# main.net
KiCad netlist of a schematic drawn in Altium Designer
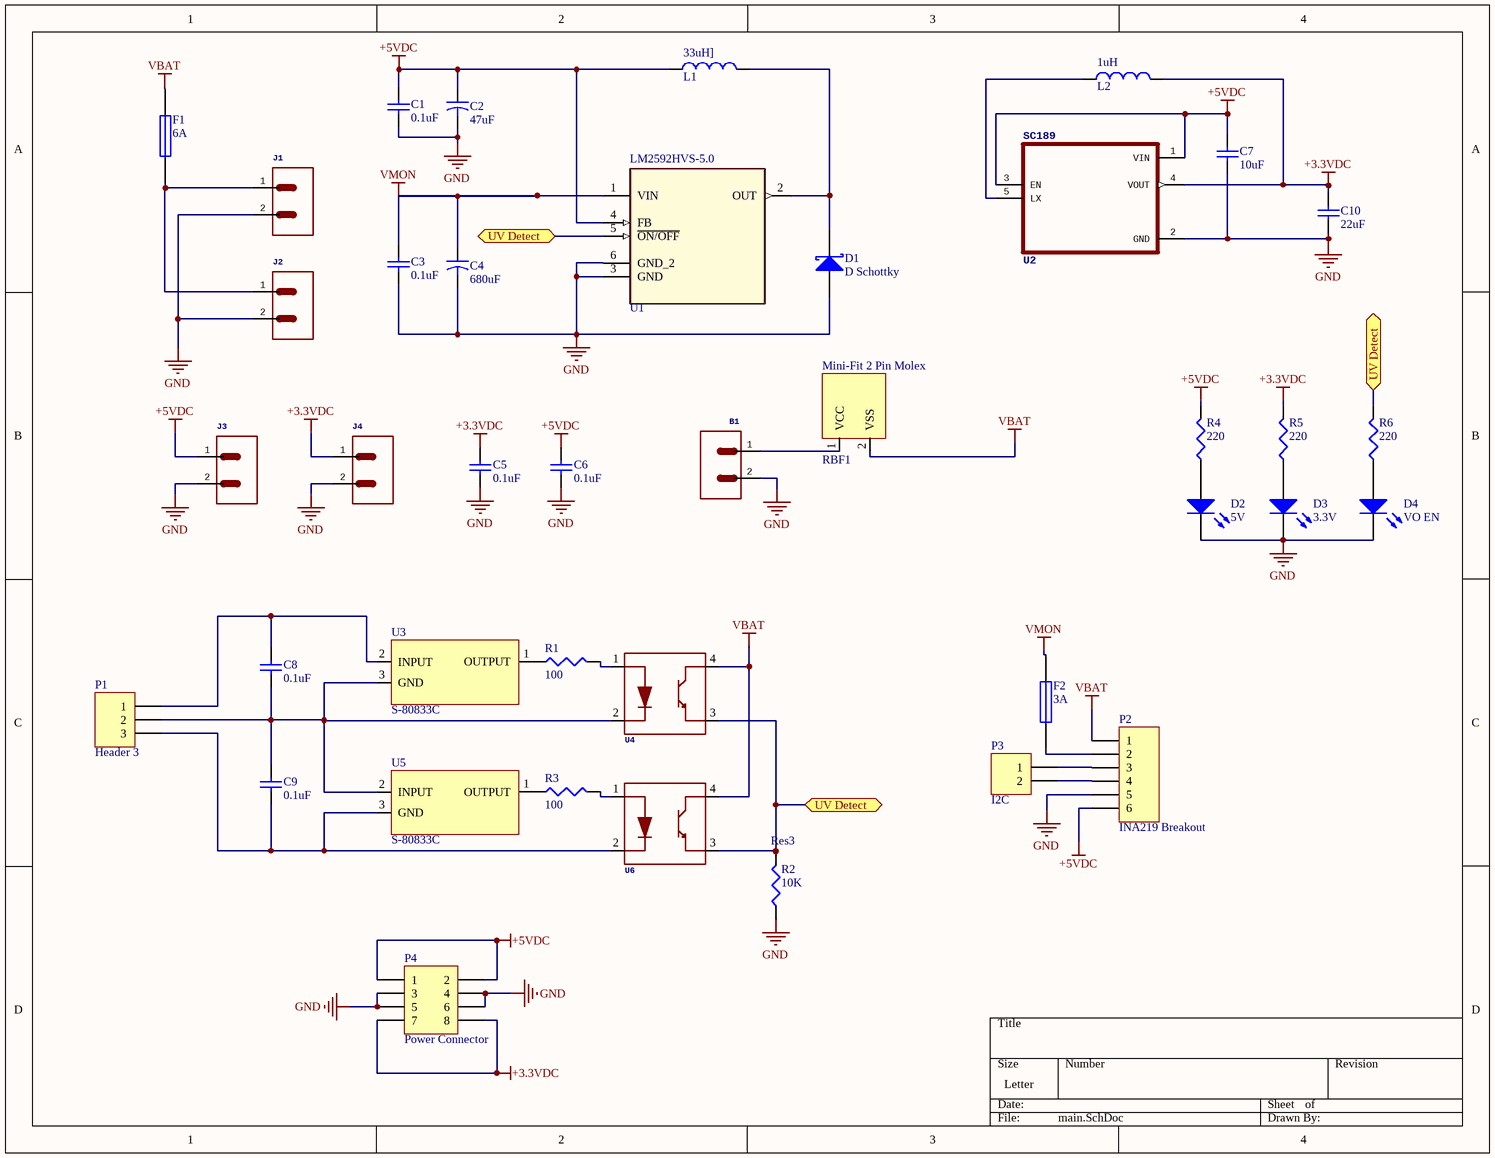
[diagram p0: main.SchDoc]

(export (version "E")
  (design (tool "Eeschema 10.0.6"))
  (components
    (comp (ref "B1")
      (value "15A 2P TERM BLOCK, BLACKtested: NO")
      (footprint "Mini-Fit 2 Pin Molex")
      (libsource (lib "Common-Parts-Library") (part "1760510000"))
    )
    (comp (ref "C1")
      (value "0.1uF")
      (footprint "C1206")
      (description "Capacitor (Semiconductor SIM Model)")
      (fields (field (name "Comment") "Cap Semi") (field (name "PUBLISHER") "Altium Limited"))
      (libsource (lib "Miscellaneous Devices") (part "Cap Semi"))
    )
    (comp (ref "C2")
      (value "47uF")
      (footprint "47 uF Cap")
      (description "Capacitor")
      (fields (field (name "Comment") "Cap2") (field (name "PUBLISHER") "Altium Limited"))
      (libsource (lib "Miscellaneous Devices") (part "Cap2"))
    )
    (comp (ref "C3")
      (value "0.1uF")
      (footprint "C1206")
      (description "Capacitor (Semiconductor SIM Model)")
      (fields (field (name "Comment") "Cap Semi") (field (name "PUBLISHER") "Altium Limited"))
      (libsource (lib "Miscellaneous Devices") (part "Cap Semi"))
    )
    (comp (ref "C4")
      (value "680uF")
      (footprint "680 uF Cap")
      (description "Capacitor")
      (fields (field (name "Comment") "Cap2") (field (name "PUBLISHER") "Altium Limited"))
      (libsource (lib "Miscellaneous Devices") (part "Cap2"))
    )
    (comp (ref "C5")
      (value "0.1uF")
      (footprint "C1206")
      (description "Capacitor (Semiconductor SIM Model)")
      (fields (field (name "Comment") "Cap Semi") (field (name "PUBLISHER") "Altium Limited"))
      (libsource (lib "Miscellaneous Devices") (part "Cap Semi"))
    )
    (comp (ref "C6")
      (value "0.1uF")
      (footprint "C1206")
      (description "Capacitor (Semiconductor SIM Model)")
      (fields (field (name "Comment") "Cap Semi") (field (name "PUBLISHER") "Altium Limited"))
      (libsource (lib "Miscellaneous Devices") (part "Cap Semi"))
    )
    (comp (ref "C7")
      (value "10uF")
      (footprint "C1206")
      (description "Capacitor (Semiconductor SIM Model)")
      (fields (field (name "Comment") "Cap Semi") (field (name "PUBLISHER") "Altium Limited"))
      (libsource (lib "Miscellaneous Devices") (part "Cap Semi"))
    )
    (comp (ref "C8")
      (value "0.1uF")
      (footprint "C1206")
      (description "Capacitor (Semiconductor SIM Model)")
      (fields (field (name "Comment") "Cap Semi") (field (name "PUBLISHER") "Altium Limited"))
      (libsource (lib "Miscellaneous Devices") (part "Cap Semi"))
    )
    (comp (ref "C9")
      (value "0.1uF")
      (footprint "C1206")
      (description "Capacitor (Semiconductor SIM Model)")
      (fields (field (name "Comment") "Cap Semi") (field (name "PUBLISHER") "Altium Limited"))
      (libsource (lib "Miscellaneous Devices") (part "Cap Semi"))
    )
    (comp (ref "C10")
      (value "22uF")
      (footprint "C1206")
      (description "Capacitor (Semiconductor SIM Model)")
      (fields (field (name "Comment") "Cap Semi") (field (name "PUBLISHER") "Altium Limited"))
      (libsource (lib "Miscellaneous Devices") (part "Cap Semi"))
    )
    (comp (ref "D1")
      (value "D Schottky")
      (footprint "SMB")
      (description "Schottky Diode")
      (fields (field (name "PUBLISHER") "Altium Limited"))
      (libsource (lib "Miscellaneous Devices") (part "D Schottky"))
    )
    (comp (ref "D2")
      (value "5V")
      (footprint "1608[0603]")
      (description "Typical RED GaAs LED")
      (fields (field (name "PUBLISHER") "Altium Limited"))
      (libsource (lib "Miscellaneous Devices") (part "LED1"))
    )
    (comp (ref "D3")
      (value "3.3V")
      (footprint "1608[0603]")
      (description "Typical RED GaAs LED")
      (fields (field (name "PUBLISHER") "Altium Limited"))
      (libsource (lib "Miscellaneous Devices") (part "LED1"))
    )
    (comp (ref "D4")
      (value "VO EN")
      (footprint "1608[0603]")
      (description "Typical RED GaAs LED")
      (fields (field (name "PUBLISHER") "Altium Limited"))
      (libsource (lib "Miscellaneous Devices") (part "LED1"))
    )
    (comp (ref "F1")
      (value "6A")
      (footprint "C1206")
      (description "Fuse")
      (fields (field (name "PUBLISHER") "Altium Limited"))
      (libsource (lib "Miscellaneous Devices") (part "Fuse 1"))
    )
    (comp (ref "F2")
      (value "3A")
      (footprint "J1-0603")
      (description "Fuse")
      (fields (field (name "PUBLISHER") "Altium Limited"))
      (libsource (lib "Miscellaneous Devices") (part "Fuse 1"))
    )
    (comp (ref "J1")
      (value "15A 2P TERM BLOCK, BLACKtested: NO")
      (footprint "1760490000")
      (libsource (lib "Common-Parts-Library") (part "1760510000"))
    )
    (comp (ref "J2")
      (value "15A 2P TERM BLOCK, BLACKtested: NO")
      (footprint "1760490000")
      (libsource (lib "Common-Parts-Library") (part "1760510000"))
    )
    (comp (ref "J3")
      (value "15A 2P TERM BLOCK, BLACKtested: NO")
      (footprint "1760490000")
      (libsource (lib "Common-Parts-Library") (part "1760510000"))
    )
    (comp (ref "J4")
      (value "15A 2P TERM BLOCK, BLACKtested: NO")
      (footprint "1760490000")
      (libsource (lib "Common-Parts-Library") (part "1760510000"))
    )
    (comp (ref "L1")
      (value "33uH]")
      (footprint "Inductor")
      (libsource (lib "CustomCompLib") (part "Inductor"))
    )
    (comp (ref "L2")
      (value "1uH")
      (footprint "INDC4532X34N")
      (libsource (lib "CustomCompLib") (part "Inductor"))
    )
    (comp (ref "P1")
      (value "Header 3")
      (footprint "HDR1X3")
      (description "Header, 3-Pin")
      (fields (field (name "PUBLISHER") "Altium Limited"))
      (libsource (lib "Miscellaneous Connectors") (part "Header 3"))
    )
    (comp (ref "P2")
      (value "INA219 Breakout")
      (footprint "HDR1X6")
      (description "Header, 6-Pin")
      (fields (field (name "PUBLISHER") "Altium Limited"))
      (libsource (lib "Miscellaneous Connectors") (part "Header 6"))
    )
    (comp (ref "P3")
      (value "I2C")
      (footprint "HDR1X2")
      (description "Header, 2-Pin")
      (fields (field (name "PUBLISHER") "Altium Limited"))
      (libsource (lib "Miscellaneous Connectors") (part "Header 2"))
    )
    (comp (ref "P4")
      (value "Power Connector")
      (footprint "HDR2X4")
      (description "Header, 4-Pin, Dual row")
      (fields (field (name "PUBLISHER") "Altium Limited"))
      (libsource (lib "Miscellaneous Connectors") (part "Header 4X2"))
    )
    (comp (ref "R1")
      (value "100")
      (footprint "J1-0603")
      (description "Resistor")
      (fields (field (name "Comment") "Res3") (field (name "PUBLISHER") "Altium Limited"))
      (libsource (lib "Miscellaneous Devices") (part "Res3"))
    )
    (comp (ref "R2")
      (value "Res3")
      (footprint "J1-0603")
      (description "Resistor")
      (fields (field (name "ALTIUM_VALUE") "10K") (field (name "PUBLISHER") "Altium Limited"))
      (libsource (lib "Miscellaneous Devices") (part "Res3"))
    )
    (comp (ref "R3")
      (value "100")
      (footprint "J1-0603")
      (description "Resistor")
      (fields (field (name "Comment") "Res3") (field (name "PUBLISHER") "Altium Limited"))
      (libsource (lib "Miscellaneous Devices") (part "Res3"))
    )
    (comp (ref "R4")
      (value "220")
      (footprint "J1-0603")
      (description "Resistor")
      (fields (field (name "Comment") "Res3") (field (name "PUBLISHER") "Altium Limited"))
      (libsource (lib "Miscellaneous Devices") (part "Res3"))
    )
    (comp (ref "R5")
      (value "220")
      (footprint "J1-0603")
      (description "Resistor")
      (fields (field (name "Comment") "Res3") (field (name "PUBLISHER") "Altium Limited"))
      (libsource (lib "Miscellaneous Devices") (part "Res3"))
    )
    (comp (ref "R6")
      (value "220")
      (footprint "J1-0603")
      (description "Resistor")
      (fields (field (name "Comment") "Res3") (field (name "PUBLISHER") "Altium Limited"))
      (libsource (lib "Miscellaneous Devices") (part "Res3"))
    )
    (comp (ref "RBF1")
      (value "Mini-Fit 2 Pin Molex")
      (footprint "Mini-Fit 2 Pin Molex")
      (libsource (lib "Common-Parts-Library") (part "5557 5569 Mini-Fit 2 Pin Molex"))
    )
    (comp (ref "U1")
      (value "LM2592HVS-5.0")
      (footprint "*TO170P1435X457-5N")
      (libsource (lib "Common-Parts-Library") (part "LM2592HVS-5.0"))
    )
    (comp (ref "U2")
      (value "SC189")
      (footprint "SOT95P280X145-5N")
      (fields (field (name "MANUFACTURER") "Semtech Corporation"))
      (libsource (lib "Common-Parts-Library") (part "SC189ZSKTRT_1"))
    )
    (comp (ref "U3")
      (value "S-80833C")
      (footprint "TO-92A")
      (libsource (lib "Common-Parts-Library") (part "S-80833C"))
    )
    (comp (ref "U4")
      (value "306060007")
      (footprint "SOP-4")
      (fields (field (name "MPN") "LTV-816S"))
      (libsource (lib "Common-Parts-Library") (part "SMD-PHOTOCOUPLER-5KV-LTV-816S(4P-4.6X6.5MM)"))
    )
    (comp (ref "U5") (value "S-80833C") (footprint "TO-92A") (libsource (lib "") (part "S-80833C_1")))
    (comp (ref "U6")
      (value "306060007")
      (footprint "SOP-4")
      (fields (field (name "MPN") "LTV-816S"))
      (libsource (lib "Common-Parts-Library") (part "SMD-PHOTOCOUPLER-5KV-LTV-816S(4P-4.6X6.5MM)"))
    )
  )
  (nets
    (net (code "1") (name "+3.3VDC") (class "Default")
      (node (ref "C10") (pin "2") (pinfunction "2_2") (pintype "passive"))
      (node (ref "C5") (pin "2") (pinfunction "2_2") (pintype "passive"))
      (node (ref "J4") (pin "1") (pinfunction "1_1") (pintype "passive"))
      (node (ref "L2") (pin "1") (pinfunction "1_1") (pintype "passive"))
      (node (ref "P4") (pin "7") (pinfunction "7_7") (pintype "passive"))
      (node (ref "P4") (pin "8") (pinfunction "8_8") (pintype "passive"))
      (node (ref "R5") (pin "2") (pinfunction "2_2") (pintype "passive"))
      (node (ref "U2") (pin "4") (pinfunction "VOUT_4") (pintype "output"))
    )
    (net (code "2") (name "+5VDC") (class "Default")
      (node (ref "C1") (pin "2") (pinfunction "2_2") (pintype "passive"))
      (node (ref "C2") (pin "1") (pinfunction "1_1") (pintype "passive"))
      (node (ref "C6") (pin "2") (pinfunction "2_2") (pintype "passive"))
      (node (ref "C7") (pin "2") (pinfunction "2_2") (pintype "passive"))
      (node (ref "J3") (pin "1") (pinfunction "1_1") (pintype "passive"))
      (node (ref "L1") (pin "2") (pinfunction "2_2") (pintype "passive"))
      (node (ref "P2") (pin "6") (pinfunction "6_6") (pintype "passive"))
      (node (ref "P4") (pin "1") (pinfunction "1_1") (pintype "passive"))
      (node (ref "P4") (pin "2") (pinfunction "2_2") (pintype "passive"))
      (node (ref "R4") (pin "2") (pinfunction "2_2") (pintype "passive"))
      (node (ref "U1") (pin "4") (pinfunction "FB_4") (pintype "input"))
      (node (ref "U2") (pin "1") (pinfunction "VIN_1") (pintype "power_in"))
      (node (ref "U2") (pin "3") (pinfunction "EN_3") (pintype "passive"))
    )
    (net (code "3") (name "/UV Detect") (class "Default")
      (node (ref "R2") (pin "2") (pinfunction "2_2") (pintype "passive"))
      (node (ref "R6") (pin "2") (pinfunction "2_2") (pintype "passive"))
      (node (ref "U1") (pin "5") (pinfunction "~{ON/OFF}_5") (pintype "input"))
      (node (ref "U4") (pin "3") (pinfunction "E_3") (pintype "passive"))
      (node (ref "U6") (pin "3") (pinfunction "E_3") (pintype "passive"))
    )
    (net (code "4") (name "GND") (class "Default")
      (node (ref "B1") (pin "2") (pinfunction "2_2") (pintype "passive"))
      (node (ref "C1") (pin "1") (pinfunction "1_1") (pintype "passive"))
      (node (ref "C10") (pin "1") (pinfunction "1_1") (pintype "passive"))
      (node (ref "C2") (pin "2") (pinfunction "2_2") (pintype "passive"))
      (node (ref "C3") (pin "1") (pinfunction "1_1") (pintype "passive"))
      (node (ref "C4") (pin "2") (pinfunction "2_2") (pintype "passive"))
      (node (ref "C5") (pin "1") (pinfunction "1_1") (pintype "passive"))
      (node (ref "C6") (pin "1") (pinfunction "1_1") (pintype "passive"))
      (node (ref "C7") (pin "1") (pinfunction "1_1") (pintype "passive"))
      (node (ref "D1") (pin "1") (pinfunction "A_1") (pintype "passive"))
      (node (ref "D2") (pin "2") (pinfunction "K_2") (pintype "passive"))
      (node (ref "D3") (pin "2") (pinfunction "K_2") (pintype "passive"))
      (node (ref "D4") (pin "2") (pinfunction "K_2") (pintype "passive"))
      (node (ref "J1") (pin "2") (pinfunction "2_2") (pintype "passive"))
      (node (ref "J2") (pin "2") (pinfunction "2_2") (pintype "passive"))
      (node (ref "J3") (pin "2") (pinfunction "2_2") (pintype "passive"))
      (node (ref "J4") (pin "2") (pinfunction "2_2") (pintype "passive"))
      (node (ref "P2") (pin "5") (pinfunction "5_5") (pintype "passive"))
      (node (ref "P4") (pin "3") (pinfunction "3_3") (pintype "passive"))
      (node (ref "P4") (pin "4") (pinfunction "4_4") (pintype "passive"))
      (node (ref "P4") (pin "5") (pinfunction "5_5") (pintype "passive"))
      (node (ref "P4") (pin "6") (pinfunction "6_6") (pintype "passive"))
      (node (ref "R2") (pin "1") (pinfunction "1_1") (pintype "passive"))
      (node (ref "U1") (pin "3") (pinfunction "GND_3") (pintype "passive"))
      (node (ref "U1") (pin "6") (pinfunction "GND_2_6") (pintype "passive"))
      (node (ref "U2") (pin "2") (pinfunction "GND_2") (pintype "power_in"))
    )
    (net (code "5") (name "Net-(D1-K)") (class "Default")
      (node (ref "D1") (pin "2") (pinfunction "K_2") (pintype "passive"))
      (node (ref "L1") (pin "1") (pinfunction "1_1") (pintype "passive"))
      (node (ref "U1") (pin "2") (pinfunction "OUT_2") (pintype "output"))
    )
    (net (code "6") (name "Net-(D2-A)") (class "Default")
      (node (ref "D2") (pin "1") (pinfunction "A_1") (pintype "passive"))
      (node (ref "R4") (pin "1") (pinfunction "1_1") (pintype "passive"))
    )
    (net (code "7") (name "Net-(D3-A)") (class "Default")
      (node (ref "D3") (pin "1") (pinfunction "A_1") (pintype "passive"))
      (node (ref "R5") (pin "1") (pinfunction "1_1") (pintype "passive"))
    )
    (net (code "8") (name "Net-(D4-A)") (class "Default")
      (node (ref "D4") (pin "1") (pinfunction "A_1") (pintype "passive"))
      (node (ref "R6") (pin "1") (pinfunction "1_1") (pintype "passive"))
    )
    (net (code "9") (name "Net-(F1-Pad1)") (class "Default")
      (node (ref "F1") (pin "1") (pinfunction "1_1") (pintype "passive"))
      (node (ref "J1") (pin "1") (pinfunction "1_1") (pintype "passive"))
      (node (ref "J2") (pin "1") (pinfunction "1_1") (pintype "passive"))
    )
    (net (code "10") (name "Net-(F2-Pad1)") (class "Default")
      (node (ref "F2") (pin "1") (pinfunction "1_1") (pintype "passive"))
      (node (ref "P2") (pin "2") (pinfunction "2_2") (pintype "passive"))
    )
    (net (code "11") (name "Net-(P2-Pad3)") (class "Default")
      (node (ref "P2") (pin "3") (pinfunction "3_3") (pintype "passive"))
      (node (ref "P3") (pin "1") (pinfunction "1_1") (pintype "passive"))
    )
    (net (code "12") (name "Net-(P2-Pad4)") (class "Default")
      (node (ref "P2") (pin "4") (pinfunction "4_4") (pintype "passive"))
      (node (ref "P3") (pin "2") (pinfunction "2_2") (pintype "passive"))
    )
    (net (code "13") (name "Net-(RBF1-VCC)") (class "Default")
      (node (ref "B1") (pin "1") (pinfunction "1_1") (pintype "passive"))
      (node (ref "RBF1") (pin "1") (pinfunction "VCC_1") (pintype "passive"))
    )
    (net (code "14") (name "Net-(U2-LX)") (class "Default")
      (node (ref "L2") (pin "2") (pinfunction "2_2") (pintype "passive"))
      (node (ref "U2") (pin "5") (pinfunction "LX_5") (pintype "passive"))
    )
    (net (code "15") (name "Net-(U3-GND)") (class "Default")
      (node (ref "C8") (pin "1") (pinfunction "1_1") (pintype "passive"))
      (node (ref "C9") (pin "2") (pinfunction "2_2") (pintype "passive"))
      (node (ref "P1") (pin "2") (pinfunction "2_2") (pintype "passive"))
      (node (ref "U3") (pin "3") (pinfunction "GND_3") (pintype "passive"))
      (node (ref "U4") (pin "2") (pinfunction "CA_2") (pintype "passive"))
      (node (ref "U5") (pin "2") (pinfunction "INPUT_2") (pintype "passive"))
    )
    (net (code "16") (name "Net-(U3-INPUT)") (class "Default")
      (node (ref "C8") (pin "2") (pinfunction "2_2") (pintype "passive"))
      (node (ref "P1") (pin "1") (pinfunction "1_1") (pintype "passive"))
      (node (ref "U3") (pin "2") (pinfunction "INPUT_2") (pintype "passive"))
    )
    (net (code "17") (name "Net-(U3-OUTPUT)") (class "Default")
      (node (ref "R1") (pin "1") (pinfunction "1_1") (pintype "passive"))
      (node (ref "U3") (pin "1") (pinfunction "OUTPUT_1") (pintype "passive"))
    )
    (net (code "18") (name "Net-(U4-AN)") (class "Default")
      (node (ref "R1") (pin "2") (pinfunction "2_2") (pintype "passive"))
      (node (ref "U4") (pin "1") (pinfunction "AN_1") (pintype "passive"))
    )
    (net (code "19") (name "Net-(U5-GND)") (class "Default")
      (node (ref "C9") (pin "1") (pinfunction "1_1") (pintype "passive"))
      (node (ref "P1") (pin "3") (pinfunction "3_3") (pintype "passive"))
      (node (ref "U5") (pin "3") (pinfunction "GND_3") (pintype "passive"))
      (node (ref "U6") (pin "2") (pinfunction "CA_2") (pintype "passive"))
    )
    (net (code "20") (name "Net-(U5-OUTPUT)") (class "Default")
      (node (ref "R3") (pin "1") (pinfunction "1_1") (pintype "passive"))
      (node (ref "U5") (pin "1") (pinfunction "OUTPUT_1") (pintype "passive"))
    )
    (net (code "21") (name "Net-(U6-AN)") (class "Default")
      (node (ref "R3") (pin "2") (pinfunction "2_2") (pintype "passive"))
      (node (ref "U6") (pin "1") (pinfunction "AN_1") (pintype "passive"))
    )
    (net (code "22") (name "VBAT") (class "Default")
      (node (ref "F1") (pin "2") (pinfunction "2_2") (pintype "passive"))
      (node (ref "P2") (pin "1") (pinfunction "1_1") (pintype "passive"))
      (node (ref "RBF1") (pin "2") (pinfunction "VSS_2") (pintype "passive"))
      (node (ref "U4") (pin "4") (pinfunction "C_4") (pintype "passive"))
      (node (ref "U6") (pin "4") (pinfunction "C_4") (pintype "passive"))
    )
    (net (code "23") (name "VMON") (class "Default")
      (node (ref "C3") (pin "2") (pinfunction "2_2") (pintype "passive"))
      (node (ref "C4") (pin "1") (pinfunction "1_1") (pintype "passive"))
      (node (ref "F2") (pin "2") (pinfunction "2_2") (pintype "passive"))
      (node (ref "U1") (pin "1") (pinfunction "VIN_1") (pintype "power_in"))
    )
  )
)
